# 4.net
KiCad netlist of a schematic drawn in EAGLE
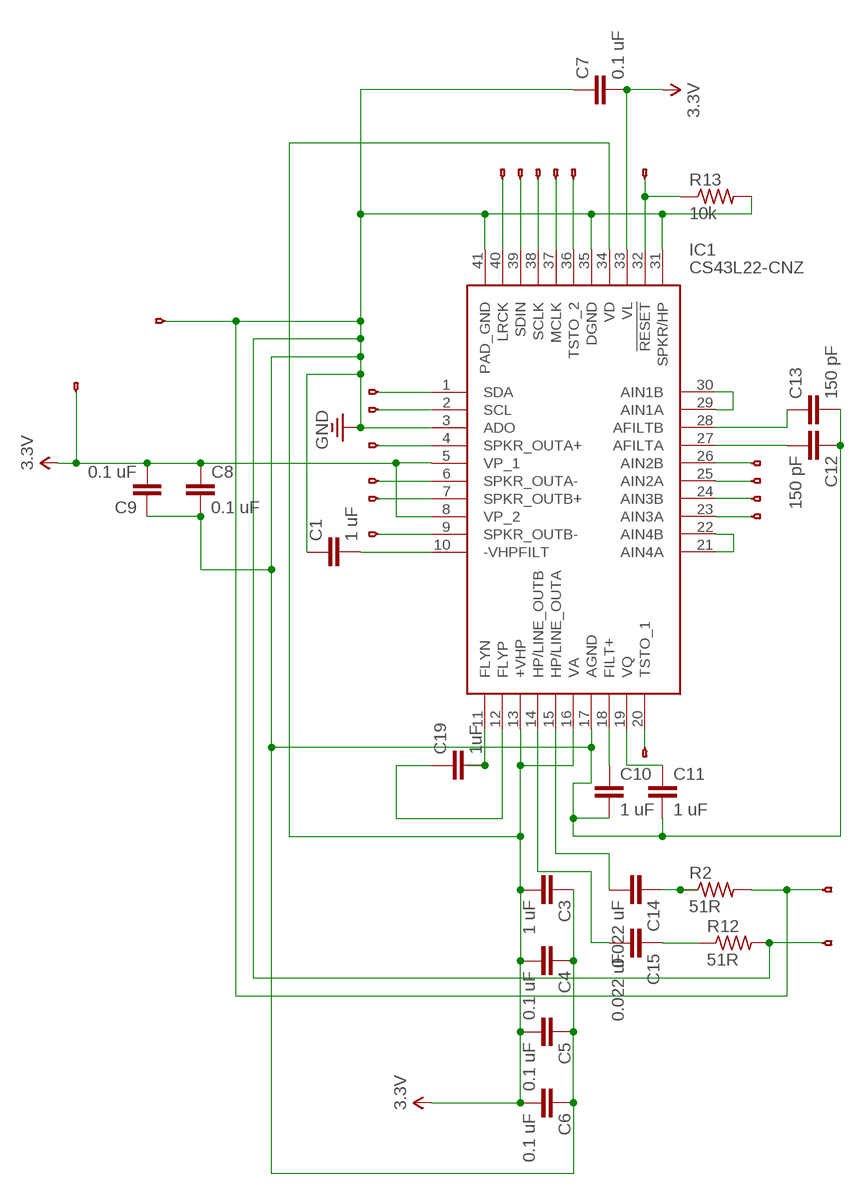
[diagram p0: schematic, sheet 1]

(export (version "E")
  (design (tool "Eeschema 10.0.6"))
  (components
    (comp (ref "C1")
      (value "1 uF")
      (footprint "eagle-import:CAP-PTH-SMALL-KIT")
      (libsource (lib "eagle-import") (part "CAPKIT"))
    )
    (comp (ref "C3")
      (value "1 uF")
      (footprint "eagle-import:CAP-PTH-SMALL-KIT")
      (libsource (lib "eagle-import") (part "CAPKIT"))
    )
    (comp (ref "C4")
      (value "0.1 uF")
      (footprint "eagle-import:CAP-PTH-SMALL-KIT")
      (libsource (lib "eagle-import") (part "CAPKIT"))
    )
    (comp (ref "C5")
      (value "0.1 uF")
      (footprint "eagle-import:CAP-PTH-SMALL-KIT")
      (libsource (lib "eagle-import") (part "CAPKIT"))
    )
    (comp (ref "C6")
      (value "0.1 uF")
      (footprint "eagle-import:CAP-PTH-SMALL-KIT")
      (libsource (lib "eagle-import") (part "CAPKIT"))
    )
    (comp (ref "C7")
      (value "0.1 uF")
      (footprint "eagle-import:CAP-PTH-SMALL-KIT")
      (libsource (lib "eagle-import") (part "CAPKIT"))
    )
    (comp (ref "C8")
      (value "0.1 uF")
      (footprint "eagle-import:CAP-PTH-SMALL-KIT")
      (libsource (lib "eagle-import") (part "CAPKIT"))
    )
    (comp (ref "C9")
      (value "0.1 uF")
      (footprint "eagle-import:CAP-PTH-SMALL-KIT")
      (libsource (lib "eagle-import") (part "CAPKIT"))
    )
    (comp (ref "C10")
      (value "1 uF")
      (footprint "eagle-import:CAP-PTH-SMALL-KIT")
      (libsource (lib "eagle-import") (part "CAPKIT"))
    )
    (comp (ref "C11")
      (value "1 uF")
      (footprint "eagle-import:CAP-PTH-SMALL-KIT")
      (libsource (lib "eagle-import") (part "CAPKIT"))
    )
    (comp (ref "C12")
      (value "150 pF")
      (footprint "eagle-import:CAP-PTH-SMALL-KIT")
      (libsource (lib "eagle-import") (part "CAPKIT"))
    )
    (comp (ref "C13")
      (value "150 pF")
      (footprint "eagle-import:CAP-PTH-SMALL-KIT")
      (libsource (lib "eagle-import") (part "CAPKIT"))
    )
    (comp (ref "C14")
      (value "0.022 uF")
      (footprint "eagle-import:CAP-PTH-SMALL-KIT")
      (libsource (lib "eagle-import") (part "CAPKIT"))
    )
    (comp (ref "C15")
      (value "0.022 uF")
      (footprint "eagle-import:CAP-PTH-SMALL-KIT")
      (libsource (lib "eagle-import") (part "CAPKIT"))
    )
    (comp (ref "C19")
      (value "1uF")
      (footprint "eagle-import:C2.5-3")
      (libsource (lib "eagle-import") (part "C2,5-3"))
    )
    (comp (ref "IC1")
      (value "CS43L22-CNZ")
      (footprint "eagle-import:QFN50P600X600X100-41N")
      (fields
        (field (name "MOUSER_PART_NUMBER") "777-CS43L22-CNZ")
        (field (name "RS_PART_NUMBER") "7165851P")
      )
      (libsource (lib "eagle-import") (part "CS43L22-CNZ"))
    )
    (comp (ref "JP1")
      (value "HEADERHOLE-HEADERHOLE")
      (footprint "eagle-import:1X1-HEADER-HOLE")
      (libsource (lib "eagle-import") (part "HEADERHOLE-HEADERHOLE"))
    )
    (comp (ref "JP2")
      (value "HEADERHOLE-HEADERHOLE")
      (footprint "eagle-import:1X1-HEADER-HOLE")
      (libsource (lib "eagle-import") (part "HEADERHOLE-HEADERHOLE"))
    )
    (comp (ref "JP3")
      (value "HEADERHOLE-HEADERHOLE")
      (footprint "eagle-import:1X1-HEADER-HOLE")
      (libsource (lib "eagle-import") (part "HEADERHOLE-HEADERHOLE"))
    )
    (comp (ref "JP4")
      (value "HEADERHOLE-HEADERHOLE")
      (footprint "eagle-import:1X1-HEADER-HOLE")
      (libsource (lib "eagle-import") (part "HEADERHOLE-HEADERHOLE"))
    )
    (comp (ref "JP5")
      (value "HEADERHOLE-HEADERHOLE")
      (footprint "eagle-import:1X1-HEADER-HOLE")
      (libsource (lib "eagle-import") (part "HEADERHOLE-HEADERHOLE"))
    )
    (comp (ref "JP6")
      (value "HEADERHOLE-HEADERHOLE")
      (footprint "eagle-import:1X1-HEADER-HOLE")
      (libsource (lib "eagle-import") (part "HEADERHOLE-HEADERHOLE"))
    )
    (comp (ref "JP7")
      (value "HEADERHOLE-HEADERHOLE")
      (footprint "eagle-import:1X1-HEADER-HOLE")
      (libsource (lib "eagle-import") (part "HEADERHOLE-HEADERHOLE"))
    )
    (comp (ref "JP8")
      (value "HEADERHOLE-HEADERHOLE")
      (footprint "eagle-import:1X1-HEADER-HOLE")
      (libsource (lib "eagle-import") (part "HEADERHOLE-HEADERHOLE"))
    )
    (comp (ref "JP9")
      (value "HEADERHOLE-HEADERHOLE")
      (footprint "eagle-import:1X1-HEADER-HOLE")
      (libsource (lib "eagle-import") (part "HEADERHOLE-HEADERHOLE"))
    )
    (comp (ref "JP10")
      (value "HEADERHOLE-HEADERHOLE")
      (footprint "eagle-import:1X1-HEADER-HOLE")
      (libsource (lib "eagle-import") (part "HEADERHOLE-HEADERHOLE"))
    )
    (comp (ref "JP11")
      (value "HEADERHOLE-HEADERHOLE")
      (footprint "eagle-import:1X1-HEADER-HOLE")
      (libsource (lib "eagle-import") (part "HEADERHOLE-HEADERHOLE"))
    )
    (comp (ref "JP12")
      (value "HEADERHOLE-HEADERHOLE")
      (footprint "eagle-import:1X1-HEADER-HOLE")
      (libsource (lib "eagle-import") (part "HEADERHOLE-HEADERHOLE"))
    )
    (comp (ref "JP13")
      (value "HEADERHOLE-HEADERHOLE")
      (footprint "eagle-import:1X1-HEADER-HOLE")
      (libsource (lib "eagle-import") (part "HEADERHOLE-HEADERHOLE"))
    )
    (comp (ref "JP14")
      (value "HEADERHOLE-HEADERHOLE")
      (footprint "eagle-import:1X1-HEADER-HOLE")
      (libsource (lib "eagle-import") (part "HEADERHOLE-HEADERHOLE"))
    )
    (comp (ref "JP15")
      (value "HEADERHOLE-HEADERHOLE")
      (footprint "eagle-import:1X1-HEADER-HOLE")
      (libsource (lib "eagle-import") (part "HEADERHOLE-HEADERHOLE"))
    )
    (comp (ref "JP16")
      (value "HEADERHOLE-HEADERHOLE")
      (footprint "eagle-import:1X1-HEADER-HOLE")
      (libsource (lib "eagle-import") (part "HEADERHOLE-HEADERHOLE"))
    )
    (comp (ref "JP17")
      (value "HEADERHOLE-HEADERHOLE")
      (footprint "eagle-import:1X1-HEADER-HOLE")
      (libsource (lib "eagle-import") (part "HEADERHOLE-HEADERHOLE"))
    )
    (comp (ref "JP18")
      (value "HEADERHOLE-HEADERHOLE")
      (footprint "eagle-import:1X1-HEADER-HOLE")
      (libsource (lib "eagle-import") (part "HEADERHOLE-HEADERHOLE"))
    )
    (comp (ref "JP19")
      (value "HEADERHOLE-HEADERHOLE")
      (footprint "eagle-import:1X1-HEADER-HOLE")
      (libsource (lib "eagle-import") (part "HEADERHOLE-HEADERHOLE"))
    )
    (comp (ref "JP23")
      (value "HEADERHOLE-HEADERHOLE")
      (footprint "eagle-import:1X1-HEADER-HOLE")
      (libsource (lib "eagle-import") (part "HEADERHOLE-HEADERHOLE"))
    )
    (comp (ref "JP24")
      (value "HEADERHOLE-HEADERHOLE")
      (footprint "eagle-import:1X1-HEADER-HOLE")
      (libsource (lib "eagle-import") (part "HEADERHOLE-HEADERHOLE"))
    )
    (comp (ref "R2")
      (value "51R")
      (footprint "eagle-import:0204V")
      (libsource (lib "eagle-import") (part "R-US_0204/2V"))
    )
    (comp (ref "R12")
      (value "51R")
      (footprint "eagle-import:0204V")
      (libsource (lib "eagle-import") (part "R-US_0204/2V"))
    )
    (comp (ref "R13")
      (value "10k")
      (footprint "eagle-import:0204V")
      (libsource (lib "eagle-import") (part "R-US_0204/2V"))
    )
  )
  (nets
    (net (code "1") (name "3.3V") (class "Default")
      (node (ref "C3") (pin "2") (pinfunction "2_2") (pintype "passive"))
      (node (ref "C4") (pin "2") (pinfunction "2_2") (pintype "passive"))
      (node (ref "C5") (pin "2") (pinfunction "2_2") (pintype "passive"))
      (node (ref "C6") (pin "2") (pinfunction "2_2") (pintype "passive"))
      (node (ref "C7") (pin "2") (pinfunction "2_2") (pintype "passive"))
      (node (ref "C8") (pin "1") (pinfunction "1_1") (pintype "passive"))
      (node (ref "C9") (pin "2") (pinfunction "2_2") (pintype "passive"))
      (node (ref "IC1") (pin "13") (pinfunction "+VHP_13") (pintype "bidirectional"))
      (node (ref "IC1") (pin "16") (pinfunction "VA_16") (pintype "bidirectional"))
      (node (ref "IC1") (pin "33") (pinfunction "VL_33") (pintype "bidirectional"))
      (node (ref "IC1") (pin "34") (pinfunction "VD_34") (pintype "bidirectional"))
      (node (ref "IC1") (pin "5") (pinfunction "VP_1_5") (pintype "bidirectional"))
      (node (ref "IC1") (pin "8") (pinfunction "VP_2_8") (pintype "bidirectional"))
      (node (ref "JP24") (pin "1") (pinfunction "P$1_1") (pintype "bidirectional"))
    )
    (net (code "2") (name "GND") (class "Default")
      (node (ref "C1") (pin "1") (pinfunction "1_1") (pintype "passive"))
      (node (ref "C10") (pin "2") (pinfunction "2_2") (pintype "passive"))
      (node (ref "C11") (pin "2") (pinfunction "2_2") (pintype "passive"))
      (node (ref "C12") (pin "1") (pinfunction "1_1") (pintype "passive"))
      (node (ref "C13") (pin "2") (pinfunction "2_2") (pintype "passive"))
      (node (ref "C3") (pin "1") (pinfunction "1_1") (pintype "passive"))
      (node (ref "C4") (pin "1") (pinfunction "1_1") (pintype "passive"))
      (node (ref "C5") (pin "1") (pinfunction "1_1") (pintype "passive"))
      (node (ref "C6") (pin "1") (pinfunction "1_1") (pintype "passive"))
      (node (ref "C7") (pin "1") (pinfunction "1_1") (pintype "passive"))
      (node (ref "C8") (pin "2") (pinfunction "2_2") (pintype "passive"))
      (node (ref "C9") (pin "1") (pinfunction "1_1") (pintype "passive"))
      (node (ref "IC1") (pin "17") (pinfunction "AGND_17") (pintype "bidirectional"))
      (node (ref "IC1") (pin "3") (pinfunction "ADO_3") (pintype "bidirectional"))
      (node (ref "IC1") (pin "31") (pinfunction "SPKR/HP_31") (pintype "bidirectional"))
      (node (ref "IC1") (pin "35") (pinfunction "DGND_35") (pintype "bidirectional"))
      (node (ref "IC1") (pin "41") (pinfunction "PAD_GND_41") (pintype "bidirectional"))
      (node (ref "JP23") (pin "1") (pinfunction "P$1_1") (pintype "bidirectional"))
      (node (ref "JP8") (pin "1") (pinfunction "P$1_1") (pintype "bidirectional"))
      (node (ref "JP9") (pin "1") (pinfunction "P$1_1") (pintype "bidirectional"))
      (node (ref "R12") (pin "2") (pinfunction "2_2") (pintype "passive"))
      (node (ref "R13") (pin "2") (pinfunction "2_2") (pintype "passive"))
      (node (ref "R2") (pin "2") (pinfunction "2_2") (pintype "passive"))
    )
    (net (code "3") (name "Net-(C14-Pad1)") (class "Default")
      (node (ref "C14") (pin "1") (pinfunction "1_1") (pintype "passive"))
      (node (ref "R2") (pin "1") (pinfunction "1_1") (pintype "passive"))
    )
    (net (code "4") (name "Net-(C15-Pad1)") (class "Default")
      (node (ref "C15") (pin "1") (pinfunction "1_1") (pintype "passive"))
      (node (ref "R12") (pin "1") (pinfunction "1_1") (pintype "passive"))
    )
    (net (code "5") (name "Net-(IC1--VHPFILT)") (class "Default")
      (node (ref "C1") (pin "2") (pinfunction "2_2") (pintype "passive"))
      (node (ref "IC1") (pin "10") (pinfunction "-VHPFILT_10") (pintype "bidirectional"))
    )
    (net (code "6") (name "Net-(IC1-AFILTA)") (class "Default")
      (node (ref "C12") (pin "2") (pinfunction "2_2") (pintype "passive"))
      (node (ref "IC1") (pin "27") (pinfunction "AFILTA_27") (pintype "bidirectional"))
    )
    (net (code "7") (name "Net-(IC1-AFILTB)") (class "Default")
      (node (ref "C13") (pin "1") (pinfunction "1_1") (pintype "passive"))
      (node (ref "IC1") (pin "28") (pinfunction "AFILTB_28") (pintype "bidirectional"))
    )
    (net (code "8") (name "Net-(IC1-AIN1A)") (class "Default")
      (node (ref "IC1") (pin "29") (pinfunction "AIN1A_29") (pintype "bidirectional"))
      (node (ref "IC1") (pin "30") (pinfunction "AIN1B_30") (pintype "bidirectional"))
    )
    (net (code "9") (name "Net-(IC1-AIN2A)") (class "Default")
      (node (ref "IC1") (pin "25") (pinfunction "AIN2A_25") (pintype "bidirectional"))
      (node (ref "JP16") (pin "1") (pinfunction "P$1_1") (pintype "bidirectional"))
    )
    (net (code "10") (name "Net-(IC1-AIN2B)") (class "Default")
      (node (ref "IC1") (pin "26") (pinfunction "AIN2B_26") (pintype "bidirectional"))
      (node (ref "JP17") (pin "1") (pinfunction "P$1_1") (pintype "bidirectional"))
    )
    (net (code "11") (name "Net-(IC1-AIN3A)") (class "Default")
      (node (ref "IC1") (pin "23") (pinfunction "AIN3A_23") (pintype "bidirectional"))
      (node (ref "JP14") (pin "1") (pinfunction "P$1_1") (pintype "bidirectional"))
    )
    (net (code "12") (name "Net-(IC1-AIN3B)") (class "Default")
      (node (ref "IC1") (pin "24") (pinfunction "AIN3B_24") (pintype "bidirectional"))
      (node (ref "JP15") (pin "1") (pinfunction "P$1_1") (pintype "bidirectional"))
    )
    (net (code "13") (name "Net-(IC1-AIN4A)") (class "Default")
      (node (ref "IC1") (pin "21") (pinfunction "AIN4A_21") (pintype "bidirectional"))
      (node (ref "IC1") (pin "22") (pinfunction "AIN4B_22") (pintype "bidirectional"))
    )
    (net (code "14") (name "Net-(IC1-FILT+)") (class "Default")
      (node (ref "C10") (pin "1") (pinfunction "1_1") (pintype "passive"))
      (node (ref "IC1") (pin "18") (pinfunction "FILT+_18") (pintype "bidirectional"))
    )
    (net (code "15") (name "Net-(IC1-FLYN)") (class "Default")
      (node (ref "C19") (pin "2") (pinfunction "2_2") (pintype "passive"))
      (node (ref "IC1") (pin "11") (pinfunction "FLYN_11") (pintype "bidirectional"))
    )
    (net (code "16") (name "Net-(IC1-FLYP)") (class "Default")
      (node (ref "C19") (pin "1") (pinfunction "1_1") (pintype "passive"))
      (node (ref "IC1") (pin "12") (pinfunction "FLYP_12") (pintype "bidirectional"))
    )
    (net (code "17") (name "Net-(IC1-HP{slash}LINE_OUTA)") (class "Default")
      (node (ref "C14") (pin "2") (pinfunction "2_2") (pintype "passive"))
      (node (ref "IC1") (pin "15") (pinfunction "HP/LINE_OUTA_15") (pintype "bidirectional"))
    )
    (net (code "18") (name "Net-(IC1-HP{slash}LINE_OUTB)") (class "Default")
      (node (ref "C15") (pin "2") (pinfunction "2_2") (pintype "passive"))
      (node (ref "IC1") (pin "14") (pinfunction "HP/LINE_OUTB_14") (pintype "bidirectional"))
    )
    (net (code "19") (name "Net-(IC1-LRCK)") (class "Default")
      (node (ref "IC1") (pin "40") (pinfunction "LRCK_40") (pintype "bidirectional"))
      (node (ref "JP6") (pin "1") (pinfunction "P$1_1") (pintype "bidirectional"))
    )
    (net (code "20") (name "Net-(IC1-MCLK)") (class "Default")
      (node (ref "IC1") (pin "37") (pinfunction "MCLK_37") (pintype "bidirectional"))
      (node (ref "JP3") (pin "1") (pinfunction "P$1_1") (pintype "bidirectional"))
    )
    (net (code "21") (name "Net-(IC1-SCL)") (class "Default")
      (node (ref "IC1") (pin "2") (pinfunction "SCL_2") (pintype "bidirectional"))
      (node (ref "JP2") (pin "1") (pinfunction "P$1_1") (pintype "bidirectional"))
    )
    (net (code "22") (name "Net-(IC1-SCLK)") (class "Default")
      (node (ref "IC1") (pin "38") (pinfunction "SCLK_38") (pintype "bidirectional"))
      (node (ref "JP4") (pin "1") (pinfunction "P$1_1") (pintype "bidirectional"))
    )
    (net (code "23") (name "Net-(IC1-SDA)") (class "Default")
      (node (ref "IC1") (pin "1") (pinfunction "SDA_1") (pintype "bidirectional"))
      (node (ref "JP1") (pin "1") (pinfunction "P$1_1") (pintype "bidirectional"))
    )
    (net (code "24") (name "Net-(IC1-SDIN)") (class "Default")
      (node (ref "IC1") (pin "39") (pinfunction "SDIN_39") (pintype "bidirectional"))
      (node (ref "JP5") (pin "1") (pinfunction "P$1_1") (pintype "bidirectional"))
    )
    (net (code "25") (name "Net-(IC1-SPKR_OUTA+)") (class "Default")
      (node (ref "IC1") (pin "4") (pinfunction "SPKR_OUTA+_4") (pintype "bidirectional"))
      (node (ref "JP10") (pin "1") (pinfunction "P$1_1") (pintype "bidirectional"))
    )
    (net (code "26") (name "Net-(IC1-SPKR_OUTA-)") (class "Default")
      (node (ref "IC1") (pin "6") (pinfunction "SPKR_OUTA-_6") (pintype "bidirectional"))
      (node (ref "JP11") (pin "1") (pinfunction "P$1_1") (pintype "bidirectional"))
    )
    (net (code "27") (name "Net-(IC1-SPKR_OUTB+)") (class "Default")
      (node (ref "IC1") (pin "7") (pinfunction "SPKR_OUTB+_7") (pintype "bidirectional"))
      (node (ref "JP12") (pin "1") (pinfunction "P$1_1") (pintype "bidirectional"))
    )
    (net (code "28") (name "Net-(IC1-SPKR_OUTB-)") (class "Default")
      (node (ref "IC1") (pin "9") (pinfunction "SPKR_OUTB-_9") (pintype "bidirectional"))
      (node (ref "JP13") (pin "1") (pinfunction "P$1_1") (pintype "bidirectional"))
    )
    (net (code "29") (name "Net-(IC1-TSTO_1)") (class "Default")
      (node (ref "IC1") (pin "20") (pinfunction "TSTO_1_20") (pintype "bidirectional"))
      (node (ref "JP18") (pin "1") (pinfunction "P$1_1") (pintype "bidirectional"))
    )
    (net (code "30") (name "Net-(IC1-TSTO_2)") (class "Default")
      (node (ref "IC1") (pin "36") (pinfunction "TSTO_2_36") (pintype "bidirectional"))
      (node (ref "JP19") (pin "1") (pinfunction "P$1_1") (pintype "bidirectional"))
    )
    (net (code "31") (name "Net-(IC1-VQ)") (class "Default")
      (node (ref "C11") (pin "1") (pinfunction "1_1") (pintype "passive"))
      (node (ref "IC1") (pin "19") (pinfunction "VQ_19") (pintype "bidirectional"))
    )
    (net (code "32") (name "Net-(IC1-~{RESET})") (class "Default")
      (node (ref "IC1") (pin "32") (pinfunction "~{RESET}_32") (pintype "bidirectional"))
      (node (ref "JP7") (pin "1") (pinfunction "P$1_1") (pintype "bidirectional"))
      (node (ref "R13") (pin "1") (pinfunction "1_1") (pintype "passive"))
    )
  )
)
